# encoder.net
KiCad netlist of a schematic drawn in EAGLE
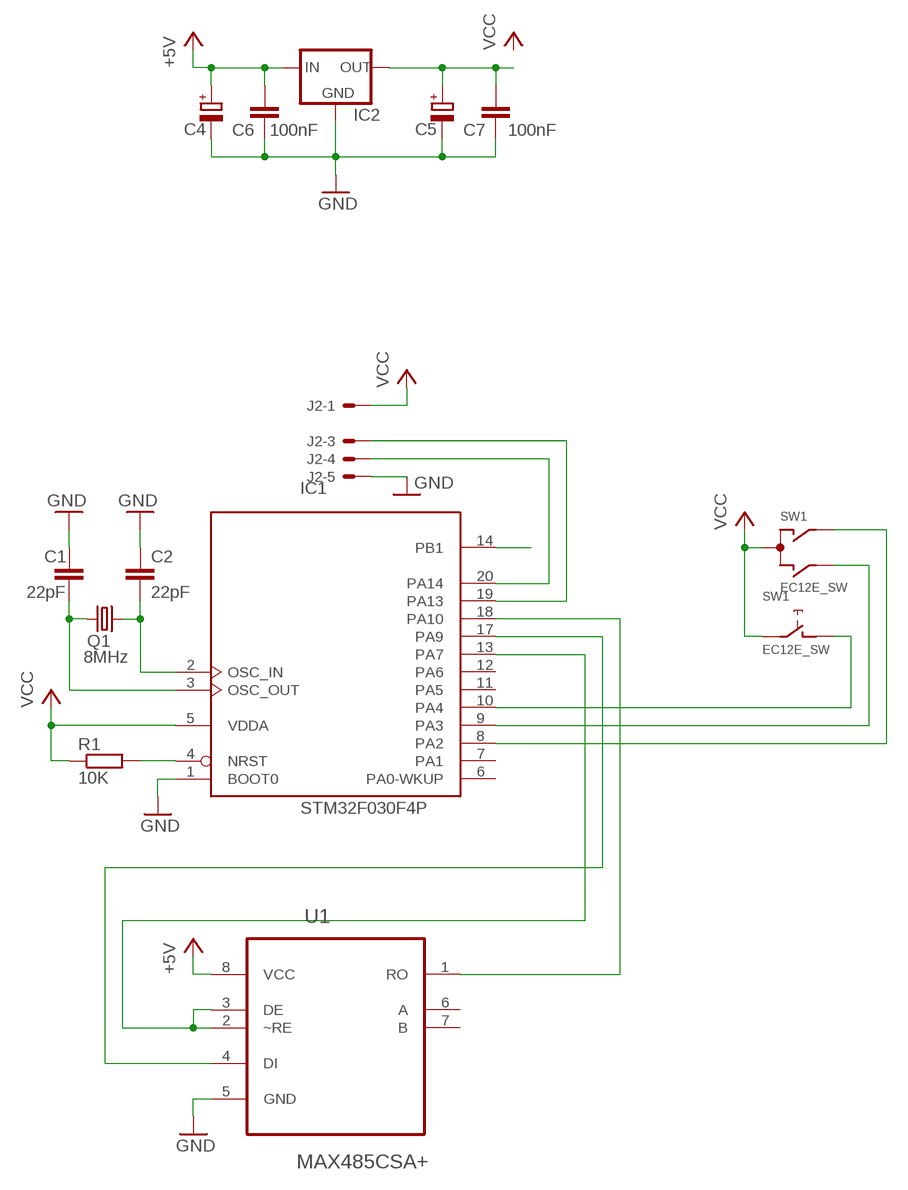
[diagram p0: schematic, sheet 1]

(export (version "E")
  (design (tool "Eeschema 10.0.6"))
  (components
    (comp (ref "C1")
      (value "22pF")
      (footprint "eagle-import:C2.5-3")
      (libsource (lib "eagle-import") (part "C2,5-3"))
    )
    (comp (ref "C2")
      (value "22pF")
      (footprint "eagle-import:C2.5-3")
      (libsource (lib "eagle-import") (part "C2,5-3"))
    )
    (comp (ref "C4")
      (value "CPOL-EU085CS-1AR")
      (footprint "eagle-import:085CS_1AR")
      (libsource (lib "eagle-import") (part "CPOL-EU085CS-1AR"))
    )
    (comp (ref "C5")
      (value "CPOL-EU085CS-1AR")
      (footprint "eagle-import:085CS_1AR")
      (libsource (lib "eagle-import") (part "CPOL-EU085CS-1AR"))
    )
    (comp (ref "C6")
      (value "100nF")
      (footprint "eagle-import:C2.5-3")
      (libsource (lib "eagle-import") (part "C2,5-3"))
    )
    (comp (ref "C7")
      (value "100nF")
      (footprint "eagle-import:C2.5-3")
      (libsource (lib "eagle-import") (part "C2,5-3"))
    )
    (comp (ref "IC1")
      (value "STM32F030F4P")
      (footprint "eagle-import:TSSOP20-I")
      (libsource (lib "eagle-import") (part "STM32F030FP4"))
    )
    (comp (ref "IC2")
      (value "78LXX")
      (footprint "eagle-import:78LXX")
      (libsource (lib "eagle-import") (part "78LXX"))
    )
    (comp (ref "J2")
      (value "22-27-2051-05")
      (footprint "eagle-import:6410-05")
      (libsource (lib "eagle-import") (part "22-?-0527-2051"))
    )
    (comp (ref "Q1")
      (value "8MHz")
      (footprint "eagle-import:HC18U-V")
      (libsource (lib "eagle-import") (part "CRYSTALHC18U-V"))
    )
    (comp (ref "R1")
      (value "10K")
      (footprint "eagle-import:R1206")
      (libsource (lib "eagle-import") (part "R-EU_R1206"))
    )
    (comp (ref "SW1")
      (value "EC12E_SW")
      (footprint "eagle-import:ALPS_EC12E_SW")
      (fields (field (name "MPN") "EC12E2424407"))
      (libsource (lib "eagle-import") (part "EC12E_SW"))
    )
    (comp (ref "U1")
      (value "MAX485CSA+")
      (footprint "eagle-import:SOIC127P600X175-8N")
      (libsource (lib "eagle-import") (part "MAX485CSA+"))
    )
  )
  (nets
    (net (code "1") (name "+5V") (class "Default")
      (node (ref "C4") (pin "+") (pinfunction "+_+") (pintype "passive"))
      (node (ref "C6") (pin "2") (pinfunction "2_2") (pintype "passive"))
      (node (ref "IC2") (pin "IN") (pinfunction "IN_IN") (pintype "input"))
      (node (ref "U1") (pin "8") (pinfunction "VCC_8") (pintype "power_in"))
    )
    (net (code "2") (name "GND") (class "Default")
      (node (ref "C1") (pin "1") (pinfunction "1_1") (pintype "passive"))
      (node (ref "C2") (pin "1") (pinfunction "1_1") (pintype "passive"))
      (node (ref "C4") (pin "-") (pinfunction "-_-") (pintype "passive"))
      (node (ref "C5") (pin "-") (pinfunction "-_-") (pintype "passive"))
      (node (ref "C6") (pin "1") (pinfunction "1_1") (pintype "passive"))
      (node (ref "C7") (pin "1") (pinfunction "1_1") (pintype "passive"))
      (node (ref "IC1") (pin "1") (pinfunction "BOOT0_1") (pintype "input"))
      (node (ref "IC2") (pin "GND") (pinfunction "GND_GND") (pintype "input"))
      (node (ref "J2") (pin "5") (pinfunction "S_5") (pintype "passive"))
      (node (ref "U1") (pin "5") (pinfunction "GND_5") (pintype "passive"))
    )
    (net (code "3") (name "Net-(C5-Pad+)") (class "Default")
      (node (ref "C5") (pin "+") (pinfunction "+_+") (pintype "passive"))
      (node (ref "C7") (pin "2") (pinfunction "2_2") (pintype "passive"))
      (node (ref "IC2") (pin "OUT") (pinfunction "OUT_OUT") (pintype "passive"))
    )
    (net (code "4") (name "Net-(IC1A-NRST)") (class "Default")
      (node (ref "IC1") (pin "4") (pinfunction "NRST_4") (pintype "bidirectional"))
      (node (ref "R1") (pin "2") (pinfunction "2_2") (pintype "passive"))
    )
    (net (code "5") (name "Net-(IC1A-OSC_IN)") (class "Default")
      (node (ref "C2") (pin "2") (pinfunction "2_2") (pintype "passive"))
      (node (ref "IC1") (pin "2") (pinfunction "OSC_IN_2") (pintype "bidirectional"))
      (node (ref "Q1") (pin "2") (pinfunction "2_2") (pintype "passive"))
    )
    (net (code "6") (name "Net-(IC1A-OSC_OUT)") (class "Default")
      (node (ref "C1") (pin "2") (pinfunction "2_2") (pintype "passive"))
      (node (ref "IC1") (pin "3") (pinfunction "OSC_OUT_3") (pintype "bidirectional"))
      (node (ref "Q1") (pin "1") (pinfunction "1_1") (pintype "passive"))
    )
    (net (code "7") (name "Net-(IC1A-PA2)") (class "Default")
      (node (ref "IC1") (pin "8") (pinfunction "PA2_8") (pintype "bidirectional"))
      (node (ref "SW1") (pin "A") (pinfunction "A_A") (pintype "passive"))
    )
    (net (code "8") (name "Net-(IC1A-PA3)") (class "Default")
      (node (ref "IC1") (pin "9") (pinfunction "PA3_9") (pintype "bidirectional"))
      (node (ref "SW1") (pin "B") (pinfunction "B_B") (pintype "passive"))
    )
    (net (code "9") (name "Net-(IC1A-PA4)") (class "Default")
      (node (ref "IC1") (pin "10") (pinfunction "PA4_10") (pintype "bidirectional"))
      (node (ref "SW1") (pin "D") (pinfunction "1_D") (pintype "passive"))
    )
    (net (code "10") (name "Net-(IC1A-PA7)") (class "Default")
      (node (ref "IC1") (pin "13") (pinfunction "PA7_13") (pintype "bidirectional"))
      (node (ref "U1") (pin "2") (pinfunction "~{RE}_2") (pintype "input"))
      (node (ref "U1") (pin "3") (pinfunction "DE_3") (pintype "input"))
    )
    (net (code "11") (name "Net-(IC1A-PA9)") (class "Default")
      (node (ref "IC1") (pin "17") (pinfunction "PA9_17") (pintype "bidirectional"))
      (node (ref "U1") (pin "4") (pinfunction "DI_4") (pintype "input"))
    )
    (net (code "12") (name "Net-(IC1A-PA10)") (class "Default")
      (node (ref "IC1") (pin "18") (pinfunction "PA10_18") (pintype "bidirectional"))
      (node (ref "U1") (pin "1") (pinfunction "RO_1") (pintype "output"))
    )
    (net (code "13") (name "Net-(IC1A-PA13)") (class "Default")
      (node (ref "IC1") (pin "19") (pinfunction "PA13_19") (pintype "bidirectional"))
      (node (ref "J2") (pin "3") (pinfunction "S_3") (pintype "passive"))
    )
    (net (code "14") (name "Net-(IC1A-PA14)") (class "Default")
      (node (ref "IC1") (pin "20") (pinfunction "PA14_20") (pintype "bidirectional"))
      (node (ref "J2") (pin "4") (pinfunction "S_4") (pintype "passive"))
    )
    (net (code "15") (name "VCC") (class "Default")
      (node (ref "IC1") (pin "5") (pinfunction "VDDA_5") (pintype "power_in"))
      (node (ref "J2") (pin "1") (pinfunction "S_1") (pintype "passive"))
      (node (ref "R1") (pin "1") (pinfunction "1_1") (pintype "passive"))
      (node (ref "SW1") (pin "C") (pinfunction "C_C") (pintype "passive"))
      (node (ref "SW1") (pin "E") (pinfunction "2_E") (pintype "passive"))
    )
    (net (code "16") (name "unconnected-(IC1A-PA0-WKUP-Pad6)") (class "Default")
      (node (ref "IC1") (pin "6") (pinfunction "PA0-WKUP_6") (pintype "bidirectional"))
    )
    (net (code "17") (name "unconnected-(IC1A-PA1-Pad7)") (class "Default")
      (node (ref "IC1") (pin "7") (pinfunction "PA1_7") (pintype "bidirectional"))
    )
    (net (code "18") (name "unconnected-(IC1A-PA5-Pad11)") (class "Default")
      (node (ref "IC1") (pin "11") (pinfunction "PA5_11") (pintype "bidirectional"))
    )
    (net (code "19") (name "unconnected-(IC1A-PA6-Pad12)") (class "Default")
      (node (ref "IC1") (pin "12") (pinfunction "PA6_12") (pintype "bidirectional"))
    )
    (net (code "20") (name "unconnected-(IC1A-PB1-Pad14)") (class "Default")
      (node (ref "IC1") (pin "14") (pinfunction "PB1_14") (pintype "bidirectional"))
    )
    (net (code "21") (name "unconnected-(U1-A-Pad6)") (class "Default")
      (node (ref "U1") (pin "6") (pinfunction "A_6") (pintype "bidirectional"))
    )
    (net (code "22") (name "unconnected-(U1-B-Pad7)") (class "Default")
      (node (ref "U1") (pin "7") (pinfunction "B_7") (pintype "bidirectional"))
    )
  )
)
